# c100_rev_b.net
KiCad netlist of a schematic drawn in EAGLE
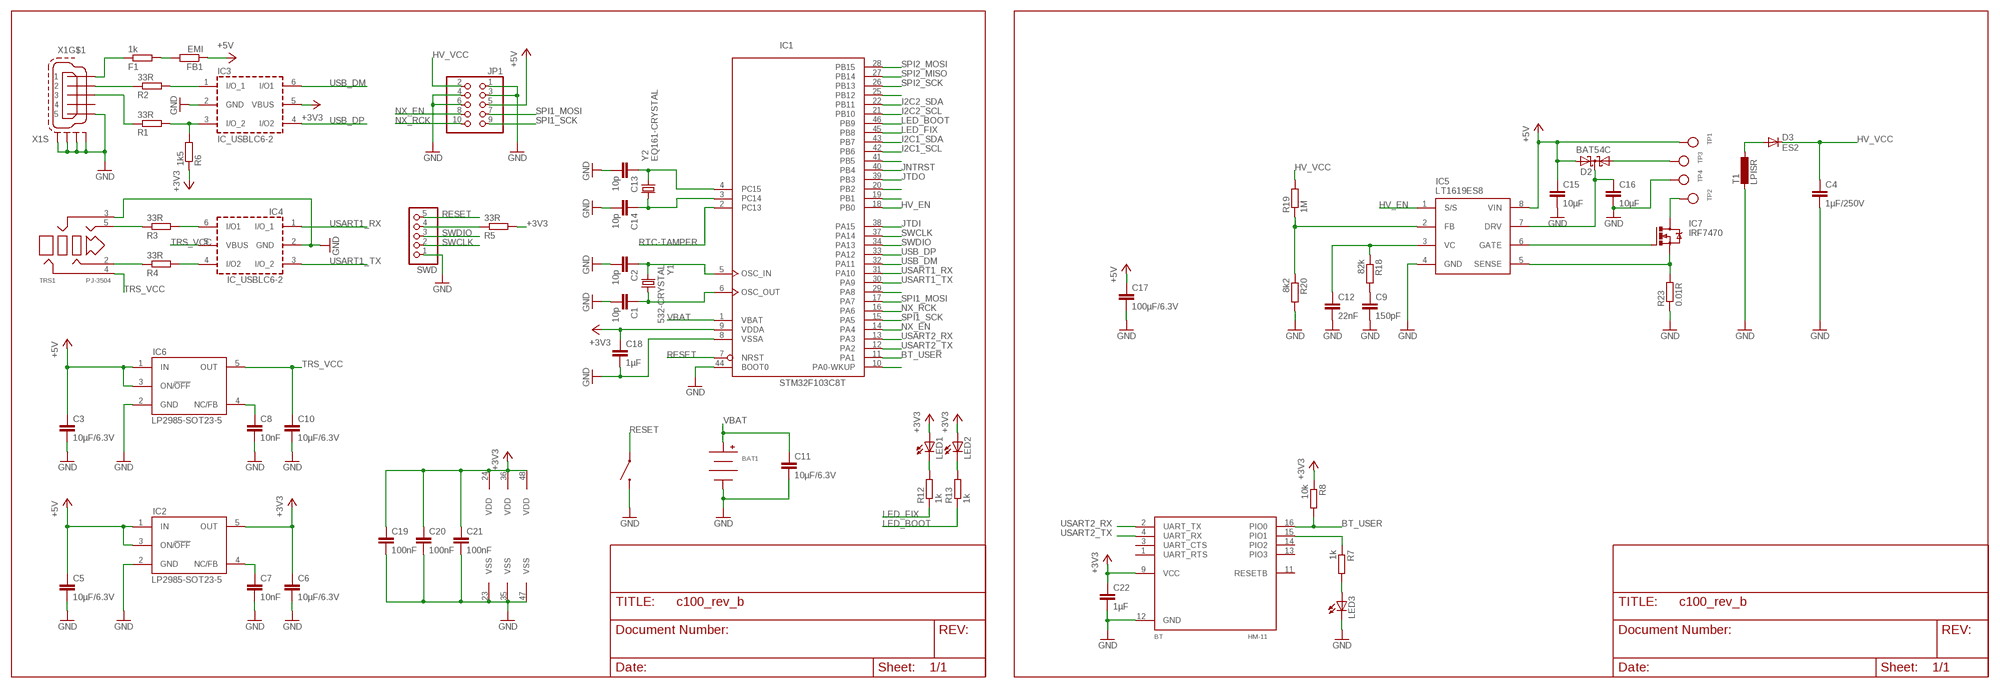
[diagram p0: schematic, sheet 1]

(export (version "E")
  (design (tool "Eeschema 10.0.6"))
  (components
    (comp (ref "BAT1")
      (value "CR1220-HOLDER")
      (footprint "eagle-import:HARWIN-CR1220")
      (libsource (lib "eagle-import") (part "CR1220-HOLDER"))
    )
    (comp (ref "BT")
      (value "HM-11")
      (footprint "eagle-import:HM-11")
      (libsource (lib "eagle-import") (part "HM-11"))
    )
    (comp (ref "C1")
      (value "10p")
      (footprint "eagle-import:C0603")
      (libsource (lib "eagle-import") (part "C-EUC0603"))
    )
    (comp (ref "C2")
      (value "10p")
      (footprint "eagle-import:C0603")
      (libsource (lib "eagle-import") (part "C-EUC0603"))
    )
    (comp (ref "C3")
      (value "10µF/6.3V")
      (footprint "eagle-import:C0603")
      (libsource (lib "eagle-import") (part "C-EUC0603"))
    )
    (comp (ref "C4")
      (value "1µF/250V")
      (footprint "eagle-import:C2220K")
      (libsource (lib "eagle-import") (part "C-EUC2220K"))
    )
    (comp (ref "C5")
      (value "10µF/6.3V")
      (footprint "eagle-import:C0603")
      (libsource (lib "eagle-import") (part "C-EUC0603"))
    )
    (comp (ref "C6")
      (value "10µF/6.3V")
      (footprint "eagle-import:C0603")
      (libsource (lib "eagle-import") (part "C-EUC0603"))
    )
    (comp (ref "C7")
      (value "10nF")
      (footprint "eagle-import:C0603")
      (libsource (lib "eagle-import") (part "C-EUC0603"))
    )
    (comp (ref "C8")
      (value "10nF")
      (footprint "eagle-import:C0603")
      (libsource (lib "eagle-import") (part "C-EUC0603"))
    )
    (comp (ref "C9")
      (value "150pF")
      (footprint "eagle-import:C0603")
      (libsource (lib "eagle-import") (part "C-EUC0603"))
    )
    (comp (ref "C10")
      (value "10µF/6.3V")
      (footprint "eagle-import:C0603")
      (libsource (lib "eagle-import") (part "C-EUC0603"))
    )
    (comp (ref "C11")
      (value "10µF/6.3V")
      (footprint "eagle-import:C0603")
      (libsource (lib "eagle-import") (part "C-EUC0603"))
    )
    (comp (ref "C12")
      (value "22nF")
      (footprint "eagle-import:C0603")
      (libsource (lib "eagle-import") (part "C-EUC0603"))
    )
    (comp (ref "C13")
      (value "10p")
      (footprint "eagle-import:C0603")
      (libsource (lib "eagle-import") (part "C-EUC0603"))
    )
    (comp (ref "C14")
      (value "10p")
      (footprint "eagle-import:C0603")
      (libsource (lib "eagle-import") (part "C-EUC0603"))
    )
    (comp (ref "C15")
      (value "10µF")
      (footprint "eagle-import:C0603")
      (libsource (lib "eagle-import") (part "C-EUC0603"))
    )
    (comp (ref "C16")
      (value "10µF")
      (footprint "eagle-import:C0603")
      (libsource (lib "eagle-import") (part "C-EUC0603"))
    )
    (comp (ref "C17")
      (value "100µF/6.3V")
      (footprint "eagle-import:C1210")
      (libsource (lib "eagle-import") (part "C-EUC1210"))
    )
    (comp (ref "C18")
      (value "1µF")
      (footprint "eagle-import:C0603")
      (libsource (lib "eagle-import") (part "C-EUC0603"))
    )
    (comp (ref "C19")
      (value "100nF")
      (footprint "eagle-import:C0603")
      (libsource (lib "eagle-import") (part "C-EUC0603"))
    )
    (comp (ref "C20")
      (value "100nF")
      (footprint "eagle-import:C0603")
      (libsource (lib "eagle-import") (part "C-EUC0603"))
    )
    (comp (ref "C21")
      (value "100nF")
      (footprint "eagle-import:C0603")
      (libsource (lib "eagle-import") (part "C-EUC0603"))
    )
    (comp (ref "C22")
      (value "1µF")
      (footprint "eagle-import:C0603")
      (libsource (lib "eagle-import") (part "C-EUC0603"))
    )
    (comp (ref "D2")
      (value "BAT54C")
      (footprint "eagle-import:SOT23")
      (libsource (lib "eagle-import") (part "BAT54C"))
    )
    (comp (ref "D3")
      (value "ES2")
      (footprint "eagle-import:DO-214AA")
      (libsource (lib "eagle-import") (part "ES2"))
    )
    (comp (ref "F1")
      (value "1k")
      (footprint "eagle-import:R0603")
      (libsource (lib "eagle-import") (part "R-EU_R0603"))
    )
    (comp (ref "FB1")
      (value "EMI")
      (footprint "eagle-import:R0603")
      (libsource (lib "eagle-import") (part "R-EU_R0603"))
    )
    (comp (ref "IC1")
      (value "STM32F103C8T")
      (footprint "eagle-import:LQFP48")
      (libsource (lib "eagle-import") (part "STM32F103CT8"))
    )
    (comp (ref "IC2")
      (value "LP2985-SOT23-5")
      (footprint "eagle-import:SOT23-5")
      (libsource (lib "eagle-import") (part "LP2985-SOT23-5"))
    )
    (comp (ref "IC3")
      (value "IC_USBLC6-2")
      (footprint "eagle-import:SOT-23-6L")
      (libsource (lib "eagle-import") (part "IC_USBLC6-2"))
    )
    (comp (ref "IC4")
      (value "IC_USBLC6-2")
      (footprint "eagle-import:SOT-23-6L")
      (libsource (lib "eagle-import") (part "IC_USBLC6-2"))
    )
    (comp (ref "IC5")
      (value "LT1619ES8")
      (footprint "eagle-import:SO8")
      (libsource (lib "eagle-import") (part "LT1619ES8"))
    )
    (comp (ref "IC6")
      (value "LP2985-SOT23-5")
      (footprint "eagle-import:SOT23-5")
      (libsource (lib "eagle-import") (part "LP2985-SOT23-5"))
    )
    (comp (ref "IC7")
      (value "IRF7470")
      (footprint "eagle-import:SO8")
      (libsource (lib "eagle-import") (part "IRF7470"))
    )
    (comp (ref "ISP")
      (value "TACT-SWITCH-40-40")
      (footprint "eagle-import:40-40")
      (libsource (lib "eagle-import") (part "TACT-SWITCH-40-40"))
    )
    (comp (ref "JP1")
      (value "PINHD-2X5_2.54-SMD")
      (footprint "eagle-import:2X05SMD")
      (libsource (lib "eagle-import") (part "PINHD-2X5_2.54-SMD"))
    )
    (comp (ref "LED1")
      (value "LEDCHIP-LED0603")
      (footprint "eagle-import:CHIP-LED0603")
      (libsource (lib "eagle-import") (part "LEDCHIP-LED0603"))
    )
    (comp (ref "LED2")
      (value "LEDCHIP-LED0603")
      (footprint "eagle-import:CHIP-LED0603")
      (libsource (lib "eagle-import") (part "LEDCHIP-LED0603"))
    )
    (comp (ref "LED3")
      (value "LEDCHIP-LED0603")
      (footprint "eagle-import:CHIP-LED0603")
      (libsource (lib "eagle-import") (part "LEDCHIP-LED0603"))
    )
    (comp (ref "R1")
      (value "33R")
      (footprint "eagle-import:R0603")
      (libsource (lib "eagle-import") (part "R-EU_R0603"))
    )
    (comp (ref "R2")
      (value "33R")
      (footprint "eagle-import:R0603")
      (libsource (lib "eagle-import") (part "R-EU_R0603"))
    )
    (comp (ref "R3")
      (value "33R")
      (footprint "eagle-import:R0603")
      (libsource (lib "eagle-import") (part "R-EU_R0603"))
    )
    (comp (ref "R4")
      (value "33R")
      (footprint "eagle-import:R0603")
      (libsource (lib "eagle-import") (part "R-EU_R0603"))
    )
    (comp (ref "R5")
      (value "33R")
      (footprint "eagle-import:R0603")
      (libsource (lib "eagle-import") (part "R-EU_R0603"))
    )
    (comp (ref "R6")
      (value "1k5")
      (footprint "eagle-import:R0603")
      (libsource (lib "eagle-import") (part "R-EU_R0603"))
    )
    (comp (ref "R7")
      (value "1k")
      (footprint "eagle-import:R0603")
      (libsource (lib "eagle-import") (part "R-EU_R0603"))
    )
    (comp (ref "R8")
      (value "10k")
      (footprint "eagle-import:R0603")
      (libsource (lib "eagle-import") (part "R-EU_R0603"))
    )
    (comp (ref "R12")
      (value "1k")
      (footprint "eagle-import:R0603")
      (libsource (lib "eagle-import") (part "R-EU_R0603"))
    )
    (comp (ref "R13")
      (value "1k")
      (footprint "eagle-import:R0603")
      (libsource (lib "eagle-import") (part "R-EU_R0603"))
    )
    (comp (ref "R18")
      (value "82k")
      (footprint "eagle-import:R0603")
      (libsource (lib "eagle-import") (part "R-EU_R0603"))
    )
    (comp (ref "R19")
      (value "1M")
      (footprint "eagle-import:M1206")
      (libsource (lib "eagle-import") (part "R-EU_M1206"))
    )
    (comp (ref "R20")
      (value "8k2")
      (footprint "eagle-import:R0603")
      (libsource (lib "eagle-import") (part "R-EU_R0603"))
    )
    (comp (ref "R23")
      (value "0.01R")
      (footprint "eagle-import:R1206")
      (libsource (lib "eagle-import") (part "R-EU_R1206"))
    )
    (comp (ref "SWD")
      (value "HEADER-1X5ROUND")
      (footprint "eagle-import:1X05_ROUND")
      (libsource (lib "eagle-import") (part "HEADER-1X5ROUND"))
    )
    (comp (ref "T1")
      (value "LPISR")
      (footprint "eagle-import:PISR")
      (libsource (lib "eagle-import") (part "LPISR"))
    )
    (comp (ref "TP1")
      (value "TESTPOINTROUND2MM")
      (footprint "eagle-import:TESTPOINT_ROUND_2MM")
      (libsource (lib "eagle-import") (part "TESTPOINTROUND2MM"))
    )
    (comp (ref "TP2")
      (value "TESTPOINTROUND2MM")
      (footprint "eagle-import:TESTPOINT_ROUND_2MM")
      (libsource (lib "eagle-import") (part "TESTPOINTROUND2MM"))
    )
    (comp (ref "TP3")
      (value "TESTPOINTROUND2MM")
      (footprint "eagle-import:TESTPOINT_ROUND_2MM")
      (libsource (lib "eagle-import") (part "TESTPOINTROUND2MM"))
    )
    (comp (ref "TP4")
      (value "TESTPOINTROUND2MM")
      (footprint "eagle-import:TESTPOINT_ROUND_2MM")
      (libsource (lib "eagle-import") (part "TESTPOINTROUND2MM"))
    )
    (comp (ref "TRS1")
      (value "PJ-3504")
      (footprint "eagle-import:YD-PJ-3504")
      (libsource (lib "eagle-import") (part "PJ-3504"))
    )
    (comp (ref "X1")
      (value "MINI-USB-SCHIELD-32005-201")
      (footprint "eagle-import:32005-201")
      (libsource (lib "eagle-import") (part "MINI-USB-SCHIELD-32005-201"))
    )
    (comp (ref "Y1")
      (value "532-CRYSTAL")
      (footprint "eagle-import:2PIN50X32")
      (libsource (lib "eagle-import") (part "532-CRYSTAL"))
    )
    (comp (ref "Y2")
      (value "EQ161-CRYSTAL")
      (footprint "eagle-import:EQ161")
      (libsource (lib "eagle-import") (part "EQ161-CRYSTAL"))
    )
  )
  (nets
    (net (code "1") (name "+3V3") (class "Default")
      (node (ref "BT") (pin "9") (pinfunction "VCC_9") (pintype "bidirectional"))
      (node (ref "C18") (pin "1") (pinfunction "1_1") (pintype "passive"))
      (node (ref "C19") (pin "1") (pinfunction "1_1") (pintype "passive"))
      (node (ref "C20") (pin "1") (pinfunction "1_1") (pintype "passive"))
      (node (ref "C21") (pin "1") (pinfunction "1_1") (pintype "passive"))
      (node (ref "C22") (pin "1") (pinfunction "1_1") (pintype "passive"))
      (node (ref "C6") (pin "1") (pinfunction "1_1") (pintype "passive"))
      (node (ref "IC1") (pin "24") (pinfunction "VDD_24") (pintype "power_in"))
      (node (ref "IC1") (pin "36") (pinfunction "VDD_36") (pintype "power_in"))
      (node (ref "IC1") (pin "48") (pinfunction "VDD_48") (pintype "power_in"))
      (node (ref "IC1") (pin "9") (pinfunction "VDDA_9") (pintype "power_in"))
      (node (ref "IC2") (pin "5") (pinfunction "OUT_5") (pintype "bidirectional"))
      (node (ref "IC3") (pin "5") (pinfunction "VBUS_5") (pintype "bidirectional"))
      (node (ref "LED1") (pin "A") (pinfunction "A_A") (pintype "passive"))
      (node (ref "LED2") (pin "A") (pinfunction "A_A") (pintype "passive"))
      (node (ref "R5") (pin "2") (pinfunction "2_2") (pintype "passive"))
      (node (ref "R6") (pin "1") (pinfunction "1_1") (pintype "passive"))
      (node (ref "R8") (pin "1") (pinfunction "1_1") (pintype "passive"))
    )
    (net (code "2") (name "+5V") (class "Default")
      (node (ref "C15") (pin "1") (pinfunction "1_1") (pintype "passive"))
      (node (ref "C17") (pin "1") (pinfunction "1_1") (pintype "passive"))
      (node (ref "C3") (pin "1") (pinfunction "1_1") (pintype "passive"))
      (node (ref "C5") (pin "1") (pinfunction "1_1") (pintype "passive"))
      (node (ref "D2") (pin "2") (pinfunction "A2_2") (pintype "passive"))
      (node (ref "FB1") (pin "1") (pinfunction "1_1") (pintype "passive"))
      (node (ref "IC2") (pin "1") (pinfunction "IN_1") (pintype "bidirectional"))
      (node (ref "IC2") (pin "3") (pinfunction "ON/~{OFF}_3") (pintype "bidirectional"))
      (node (ref "IC5") (pin "8") (pinfunction "VIN_8") (pintype "bidirectional"))
      (node (ref "IC6") (pin "1") (pinfunction "IN_1") (pintype "bidirectional"))
      (node (ref "IC6") (pin "3") (pinfunction "ON/~{OFF}_3") (pintype "bidirectional"))
      (node (ref "JP1") (pin "5") (pinfunction "5_5") (pintype "passive"))
      (node (ref "TP1") (pin "P$1") (pinfunction "P$1_P$1") (pintype "bidirectional"))
    )
    (net (code "3") (name "/BT_USER") (class "Default")
      (node (ref "BT") (pin "16") (pinfunction "PIO0_16") (pintype "bidirectional"))
      (node (ref "IC1") (pin "11") (pinfunction "PA1_11") (pintype "bidirectional"))
      (node (ref "R8") (pin "2") (pinfunction "2_2") (pintype "passive"))
    )
    (net (code "4") (name "/HV_EN") (class "Default")
      (node (ref "IC1") (pin "18") (pinfunction "PB0_18") (pintype "bidirectional"))
      (node (ref "IC5") (pin "1") (pinfunction "S/S_1") (pintype "bidirectional"))
    )
    (net (code "5") (name "/HV_VCC") (class "Default")
      (node (ref "C4") (pin "1") (pinfunction "1_1") (pintype "passive"))
      (node (ref "D3") (pin "C") (pinfunction "C_C") (pintype "passive"))
      (node (ref "JP1") (pin "2") (pinfunction "2_2") (pintype "passive"))
      (node (ref "R19") (pin "2") (pinfunction "2_2") (pintype "passive"))
    )
    (net (code "6") (name "/I2C1_SCL") (class "Default")
      (node (ref "IC1") (pin "42") (pinfunction "PB6_42") (pintype "bidirectional"))
    )
    (net (code "7") (name "/I2C1_SDA") (class "Default")
      (node (ref "IC1") (pin "43") (pinfunction "PB7_43") (pintype "bidirectional"))
    )
    (net (code "8") (name "/I2C2_SCL") (class "Default")
      (node (ref "IC1") (pin "21") (pinfunction "PB10_21") (pintype "bidirectional"))
    )
    (net (code "9") (name "/I2C2_SDA") (class "Default")
      (node (ref "IC1") (pin "22") (pinfunction "PB11_22") (pintype "bidirectional"))
    )
    (net (code "10") (name "/JNTRST") (class "Default")
      (node (ref "IC1") (pin "40") (pinfunction "PB4_40") (pintype "bidirectional"))
    )
    (net (code "11") (name "/JTDI") (class "Default")
      (node (ref "IC1") (pin "38") (pinfunction "PA15_38") (pintype "bidirectional"))
    )
    (net (code "12") (name "/JTDO") (class "Default")
      (node (ref "IC1") (pin "39") (pinfunction "PB3_39") (pintype "bidirectional"))
    )
    (net (code "13") (name "/LED_BOOT") (class "Default")
      (node (ref "IC1") (pin "46") (pinfunction "PB9_46") (pintype "bidirectional"))
      (node (ref "R13") (pin "1") (pinfunction "1_1") (pintype "passive"))
    )
    (net (code "14") (name "/LED_FIX") (class "Default")
      (node (ref "IC1") (pin "45") (pinfunction "PB8_45") (pintype "bidirectional"))
      (node (ref "R12") (pin "1") (pinfunction "1_1") (pintype "passive"))
    )
    (net (code "15") (name "/NX_EN") (class "Default")
      (node (ref "IC1") (pin "14") (pinfunction "PA4_14") (pintype "bidirectional"))
      (node (ref "JP1") (pin "8") (pinfunction "8_8") (pintype "passive"))
    )
    (net (code "16") (name "/NX_RCK") (class "Default")
      (node (ref "IC1") (pin "16") (pinfunction "PA6_16") (pintype "bidirectional"))
      (node (ref "JP1") (pin "10") (pinfunction "10_10") (pintype "passive"))
    )
    (net (code "17") (name "/RESET") (class "Default")
      (node (ref "IC1") (pin "7") (pinfunction "NRST_7") (pintype "bidirectional"))
      (node (ref "ISP") (pin "3") (pinfunction "P$2_3") (pintype "bidirectional"))
      (node (ref "ISP") (pin "4") (pinfunction "P$2_4") (pintype "bidirectional"))
      (node (ref "SWD") (pin "5") (pinfunction "5_5") (pintype "passive"))
    )
    (net (code "18") (name "/RTC-TAMPER") (class "Default")
      (node (ref "IC1") (pin "2") (pinfunction "PC13_2") (pintype "bidirectional"))
    )
    (net (code "19") (name "/SPI1_MOSI") (class "Default")
      (node (ref "IC1") (pin "17") (pinfunction "PA7_17") (pintype "bidirectional"))
      (node (ref "JP1") (pin "7") (pinfunction "7_7") (pintype "passive"))
    )
    (net (code "20") (name "/SPI1_SCK") (class "Default")
      (node (ref "IC1") (pin "15") (pinfunction "PA5_15") (pintype "bidirectional"))
      (node (ref "JP1") (pin "9") (pinfunction "9_9") (pintype "passive"))
    )
    (net (code "21") (name "/SPI2_MISO") (class "Default")
      (node (ref "IC1") (pin "27") (pinfunction "PB14_27") (pintype "bidirectional"))
    )
    (net (code "22") (name "/SPI2_MOSI") (class "Default")
      (node (ref "IC1") (pin "28") (pinfunction "PB15_28") (pintype "bidirectional"))
    )
    (net (code "23") (name "/SPI2_SCK") (class "Default")
      (node (ref "IC1") (pin "26") (pinfunction "PB13_26") (pintype "bidirectional"))
    )
    (net (code "24") (name "/SWCLK") (class "Default")
      (node (ref "IC1") (pin "37") (pinfunction "PA14_37") (pintype "bidirectional"))
      (node (ref "SWD") (pin "2") (pinfunction "2_2") (pintype "passive"))
    )
    (net (code "25") (name "/SWDIO") (class "Default")
      (node (ref "IC1") (pin "34") (pinfunction "PA13_34") (pintype "bidirectional"))
      (node (ref "SWD") (pin "3") (pinfunction "3_3") (pintype "passive"))
    )
    (net (code "26") (name "/TRS_VCC") (class "Default")
      (node (ref "C10") (pin "1") (pinfunction "1_1") (pintype "passive"))
      (node (ref "IC4") (pin "5") (pinfunction "VBUS_5") (pintype "bidirectional"))
      (node (ref "IC6") (pin "5") (pinfunction "OUT_5") (pintype "bidirectional"))
      (node (ref "TRS1") (pin "4") (pinfunction "4_4") (pintype "bidirectional"))
    )
    (net (code "27") (name "/USART1_RX") (class "Default")
      (node (ref "IC1") (pin "31") (pinfunction "PA10_31") (pintype "bidirectional"))
      (node (ref "IC4") (pin "1") (pinfunction "I/O_1_1") (pintype "bidirectional"))
    )
    (net (code "28") (name "/USART1_TX") (class "Default")
      (node (ref "IC1") (pin "30") (pinfunction "PA9_30") (pintype "bidirectional"))
      (node (ref "IC4") (pin "3") (pinfunction "I/O_2_3") (pintype "bidirectional"))
    )
    (net (code "29") (name "/USART2_RX") (class "Default")
      (node (ref "BT") (pin "2") (pinfunction "UART_TX_2") (pintype "bidirectional"))
      (node (ref "IC1") (pin "13") (pinfunction "PA3_13") (pintype "bidirectional"))
    )
    (net (code "30") (name "/USART2_TX") (class "Default")
      (node (ref "BT") (pin "4") (pinfunction "UART_RX_4") (pintype "bidirectional"))
      (node (ref "IC1") (pin "12") (pinfunction "PA2_12") (pintype "bidirectional"))
    )
    (net (code "31") (name "/USB_DM") (class "Default")
      (node (ref "IC1") (pin "32") (pinfunction "PA11_32") (pintype "bidirectional"))
      (node (ref "IC3") (pin "6") (pinfunction "I/O1_6") (pintype "bidirectional"))
    )
    (net (code "32") (name "/USB_DP") (class "Default")
      (node (ref "IC1") (pin "33") (pinfunction "PA12_33") (pintype "bidirectional"))
      (node (ref "IC3") (pin "4") (pinfunction "I/O2_4") (pintype "bidirectional"))
    )
    (net (code "33") (name "/VBAT") (class "Default")
      (node (ref "BAT1") (pin "POS") (pinfunction "POS_POS") (pintype "bidirectional"))
      (node (ref "C11") (pin "1") (pinfunction "1_1") (pintype "passive"))
      (node (ref "IC1") (pin "1") (pinfunction "VBAT_1") (pintype "power_in"))
    )
    (net (code "34") (name "GND") (class "Default")
      (node (ref "BAT1") (pin "NEG") (pinfunction "NEG_NEG") (pintype "bidirectional"))
      (node (ref "BT") (pin "12") (pinfunction "GND_12") (pintype "bidirectional"))
      (node (ref "C1") (pin "2") (pinfunction "2_2") (pintype "passive"))
      (node (ref "C10") (pin "2") (pinfunction "2_2") (pintype "passive"))
      (node (ref "C11") (pin "2") (pinfunction "2_2") (pintype "passive"))
      (node (ref "C12") (pin "2") (pinfunction "2_2") (pintype "passive"))
      (node (ref "C13") (pin "2") (pinfunction "2_2") (pintype "passive"))
      (node (ref "C14") (pin "2") (pinfunction "2_2") (pintype "passive"))
      (node (ref "C15") (pin "2") (pinfunction "2_2") (pintype "passive"))
      (node (ref "C16") (pin "2") (pinfunction "2_2") (pintype "passive"))
      (node (ref "C17") (pin "2") (pinfunction "2_2") (pintype "passive"))
      (node (ref "C18") (pin "2") (pinfunction "2_2") (pintype "passive"))
      (node (ref "C19") (pin "2") (pinfunction "2_2") (pintype "passive"))
      (node (ref "C2") (pin "2") (pinfunction "2_2") (pintype "passive"))
      (node (ref "C20") (pin "2") (pinfunction "2_2") (pintype "passive"))
      (node (ref "C21") (pin "2") (pinfunction "2_2") (pintype "passive"))
      (node (ref "C22") (pin "2") (pinfunction "2_2") (pintype "passive"))
      (node (ref "C3") (pin "2") (pinfunction "2_2") (pintype "passive"))
      (node (ref "C4") (pin "2") (pinfunction "2_2") (pintype "passive"))
      (node (ref "C5") (pin "2") (pinfunction "2_2") (pintype "passive"))
      (node (ref "C6") (pin "2") (pinfunction "2_2") (pintype "passive"))
      (node (ref "C7") (pin "2") (pinfunction "2_2") (pintype "passive"))
      (node (ref "C8") (pin "2") (pinfunction "2_2") (pintype "passive"))
      (node (ref "C9") (pin "2") (pinfunction "2_2") (pintype "passive"))
      (node (ref "IC1") (pin "23") (pinfunction "VSS_23") (pintype "power_in"))
      (node (ref "IC1") (pin "35") (pinfunction "VSS_35") (pintype "power_in"))
      (node (ref "IC1") (pin "44") (pinfunction "BOOT0_44") (pintype "input"))
      (node (ref "IC1") (pin "47") (pinfunction "VSS_47") (pintype "power_in"))
      (node (ref "IC1") (pin "8") (pinfunction "VSSA_8") (pintype "power_in"))
      (node (ref "IC2") (pin "2") (pinfunction "GND_2") (pintype "bidirectional"))
      (node (ref "IC3") (pin "2") (pinfunction "GND_2") (pintype "bidirectional"))
      (node (ref "IC4") (pin "2") (pinfunction "GND_2") (pintype "bidirectional"))
      (node (ref "IC5") (pin "4") (pinfunction "GND_4") (pintype "bidirectional"))
      (node (ref "IC6") (pin "2") (pinfunction "GND_2") (pintype "bidirectional"))
      (node (ref "ISP") (pin "1") (pinfunction "P$1_1") (pintype "bidirectional"))
      (node (ref "ISP") (pin "2") (pinfunction "P$1_2") (pintype "bidirectional"))
      (node (ref "JP1") (pin "1") (pinfunction "1_1") (pintype "passive"))
      (node (ref "JP1") (pin "3") (pinfunction "3_3") (pintype "passive"))
      (node (ref "JP1") (pin "4") (pinfunction "4_4") (pintype "passive"))
      (node (ref "JP1") (pin "6") (pinfunction "6_6") (pintype "passive"))
      (node (ref "LED3") (pin "C") (pinfunction "C_C") (pintype "passive"))
      (node (ref "R20") (pin "2") (pinfunction "2_2") (pintype "passive"))
      (node (ref "R23") (pin "1") (pinfunction "1_1") (pintype "passive"))
      (node (ref "SWD") (pin "1") (pinfunction "1_1") (pintype "passive"))
      (node (ref "T1") (pin "P$2") (pinfunction "2_P$2") (pintype "passive"))
      (node (ref "TP4") (pin "P$1") (pinfunction "P$1_P$1") (pintype "bidirectional"))
      (node (ref "TRS1") (pin "3") (pinfunction "3_3") (pintype "bidirectional"))
      (node (ref "X1") (pin "5") (pinfunction "5_5") (pintype "passive"))
      (node (ref "X1") (pin "M1") (pinfunction "S1_M1") (pintype "passive"))
      (node (ref "X1") (pin "M2") (pinfunction "S2_M2") (pintype "passive"))
      (node (ref "X1") (pin "M3") (pinfunction "S3_M3") (pintype "passive"))
      (node (ref "X1") (pin "M4") (pinfunction "S4_M4") (pintype "passive"))
    )
    (net (code "35") (name "Net-(BT-PIO1)") (class "Default")
      (node (ref "BT") (pin "15") (pinfunction "PIO1_15") (pintype "bidirectional"))
      (node (ref "R7") (pin "1") (pinfunction "1_1") (pintype "passive"))
    )
    (net (code "36") (name "Net-(C9-Pad1)") (class "Default")
      (node (ref "C9") (pin "1") (pinfunction "1_1") (pintype "passive"))
      (node (ref "R18") (pin "2") (pinfunction "2_2") (pintype "passive"))
    )
    (net (code "37") (name "Net-(D2-A1)") (class "Default")
      (node (ref "D2") (pin "1") (pinfunction "A1_1") (pintype "passive"))
      (node (ref "TP3") (pin "P$1") (pinfunction "P$1_P$1") (pintype "bidirectional"))
    )
    (net (code "38") (name "Net-(D2-CC)") (class "Default")
      (node (ref "C16") (pin "1") (pinfunction "1_1") (pintype "passive"))
      (node (ref "D2") (pin "3") (pinfunction "CC_3") (pintype "passive"))
      (node (ref "IC5") (pin "7") (pinfunction "DRV_7") (pintype "bidirectional"))
    )
    (net (code "39") (name "Net-(F1-Pad1)") (class "Default")
      (node (ref "F1") (pin "1") (pinfunction "1_1") (pintype "passive"))
      (node (ref "X1") (pin "1") (pinfunction "1_1") (pintype "passive"))
    )
    (net (code "40") (name "Net-(F1-Pad2)") (class "Default")
      (node (ref "F1") (pin "2") (pinfunction "2_2") (pintype "passive"))
      (node (ref "FB1") (pin "2") (pinfunction "2_2") (pintype "passive"))
    )
    (net (code "41") (name "Net-(IC1A-OSC_IN)") (class "Default")
      (node (ref "C2") (pin "1") (pinfunction "1_1") (pintype "passive"))
      (node (ref "IC1") (pin "5") (pinfunction "OSC_IN_5") (pintype "bidirectional"))
      (node (ref "Y1") (pin "P$2") (pinfunction "2_P$2") (pintype "passive"))
    )
    (net (code "42") (name "Net-(IC1A-OSC_OUT)") (class "Default")
      (node (ref "C1") (pin "1") (pinfunction "1_1") (pintype "passive"))
      (node (ref "IC1") (pin "6") (pinfunction "OSC_OUT_6") (pintype "bidirectional"))
      (node (ref "Y1") (pin "P$1") (pinfunction "1_P$1") (pintype "passive"))
    )
    (net (code "43") (name "Net-(IC1A-PC14)") (class "Default")
      (node (ref "C14") (pin "1") (pinfunction "1_1") (pintype "passive"))
      (node (ref "IC1") (pin "3") (pinfunction "PC14_3") (pintype "bidirectional"))
      (node (ref "Y2") (pin "P$2") (pinfunction "2_P$2") (pintype "passive"))
    )
    (net (code "44") (name "Net-(IC1A-PC15)") (class "Default")
      (node (ref "C13") (pin "1") (pinfunction "1_1") (pintype "passive"))
      (node (ref "IC1") (pin "4") (pinfunction "PC15_4") (pintype "bidirectional"))
      (node (ref "Y2") (pin "P$1") (pinfunction "1_P$1") (pintype "passive"))
    )
    (net (code "45") (name "Net-(IC2-NC{slash}FB)") (class "Default")
      (node (ref "C7") (pin "1") (pinfunction "1_1") (pintype "passive"))
      (node (ref "IC2") (pin "4") (pinfunction "NC/FB_4") (pintype "bidirectional"))
    )
    (net (code "46") (name "Net-(IC3-I{slash}O_1)") (class "Default")
      (node (ref "IC3") (pin "1") (pinfunction "I/O_1_1") (pintype "bidirectional"))
      (node (ref "R2") (pin "2") (pinfunction "2_2") (pintype "passive"))
    )
    (net (code "47") (name "Net-(IC3-I{slash}O_2)") (class "Default")
      (node (ref "IC3") (pin "3") (pinfunction "I/O_2_3") (pintype "bidirectional"))
      (node (ref "R1") (pin "2") (pinfunction "2_2") (pintype "passive"))
      (node (ref "R6") (pin "2") (pinfunction "2_2") (pintype "passive"))
    )
    (net (code "48") (name "Net-(IC4-I{slash}O1)") (class "Default")
      (node (ref "IC4") (pin "6") (pinfunction "I/O1_6") (pintype "bidirectional"))
      (node (ref "R3") (pin "2") (pinfunction "2_2") (pintype "passive"))
    )
    (net (code "49") (name "Net-(IC4-I{slash}O2)") (class "Default")
      (node (ref "IC4") (pin "4") (pinfunction "I/O2_4") (pintype "bidirectional"))
      (node (ref "R4") (pin "2") (pinfunction "2_2") (pintype "passive"))
    )
    (net (code "50") (name "Net-(IC5-FB)") (class "Default")
      (node (ref "IC5") (pin "2") (pinfunction "FB_2") (pintype "bidirectional"))
      (node (ref "R19") (pin "1") (pinfunction "1_1") (pintype "passive"))
      (node (ref "R20") (pin "1") (pinfunction "1_1") (pintype "passive"))
    )
    (net (code "51") (name "Net-(IC5-GATE)") (class "Default")
      (node (ref "IC5") (pin "6") (pinfunction "GATE_6") (pintype "bidirectional"))
      (node (ref "IC7") (pin "4") (pinfunction "G_4") (pintype "passive"))
    )
    (net (code "52") (name "Net-(IC5-SENSE)") (class "Default")
      (node (ref "IC5") (pin "5") (pinfunction "SENSE_5") (pintype "bidirectional"))
      (node (ref "IC7") (pin "1") (pinfunction "S_1") (pintype "passive"))
      (node (ref "IC7") (pin "2") (pinfunction "S_2") (pintype "passive"))
      (node (ref "IC7") (pin "3") (pinfunction "S_3") (pintype "passive"))
      (node (ref "R23") (pin "2") (pinfunction "2_2") (pintype "passive"))
    )
    (net (code "53") (name "Net-(IC5-VC)") (class "Default")
      (node (ref "C12") (pin "1") (pinfunction "1_1") (pintype "passive"))
      (node (ref "IC5") (pin "3") (pinfunction "VC_3") (pintype "bidirectional"))
      (node (ref "R18") (pin "1") (pinfunction "1_1") (pintype "passive"))
    )
    (net (code "54") (name "Net-(IC6-NC{slash}FB)") (class "Default")
      (node (ref "C8") (pin "1") (pinfunction "1_1") (pintype "passive"))
      (node (ref "IC6") (pin "4") (pinfunction "NC/FB_4") (pintype "bidirectional"))
    )
    (net (code "55") (name "Net-(IC7-D-Pad5)") (class "Default")
      (node (ref "IC7") (pin "5") (pinfunction "D_5") (pintype "passive"))
      (node (ref "IC7") (pin "6") (pinfunction "D_6") (pintype "passive"))
      (node (ref "IC7") (pin "7") (pinfunction "D_7") (pintype "passive"))
      (node (ref "IC7") (pin "8") (pinfunction "D_8") (pintype "passive"))
      (node (ref "TP2") (pin "P$1") (pinfunction "P$1_P$1") (pintype "bidirectional"))
    )
    (net (code "56") (name "Net-(LED1-PadC)") (class "Default")
      (node (ref "LED1") (pin "C") (pinfunction "C_C") (pintype "passive"))
      (node (ref "R12") (pin "2") (pinfunction "2_2") (pintype "passive"))
    )
    (net (code "57") (name "Net-(LED2-PadC)") (class "Default")
      (node (ref "LED2") (pin "C") (pinfunction "C_C") (pintype "passive"))
      (node (ref "R13") (pin "2") (pinfunction "2_2") (pintype "passive"))
    )
    (net (code "58") (name "Net-(LED3-PadA)") (class "Default")
      (node (ref "LED3") (pin "A") (pinfunction "A_A") (pintype "passive"))
      (node (ref "R7") (pin "2") (pinfunction "2_2") (pintype "passive"))
    )
    (net (code "59") (name "Net-(R1-Pad1)") (class "Default")
      (node (ref "R1") (pin "1") (pinfunction "1_1") (pintype "passive"))
      (node (ref "X1") (pin "3") (pinfunction "3_3") (pintype "passive"))
    )
    (net (code "60") (name "Net-(R2-Pad1)") (class "Default")
      (node (ref "R2") (pin "1") (pinfunction "1_1") (pintype "passive"))
      (node (ref "X1") (pin "2") (pinfunction "2_2") (pintype "passive"))
    )
    (net (code "61") (name "Net-(R3-Pad1)") (class "Default")
      (node (ref "R3") (pin "1") (pinfunction "1_1") (pintype "passive"))
      (node (ref "TRS1") (pin "5") (pinfunction "5_5") (pintype "bidirectional"))
    )
    (net (code "62") (name "Net-(R4-Pad1)") (class "Default")
      (node (ref "R4") (pin "1") (pinfunction "1_1") (pintype "passive"))
      (node (ref "TRS1") (pin "2") (pinfunction "2_2") (pintype "bidirectional"))
    )
    (net (code "63") (name "Net-(R5-Pad1)") (class "Default")
      (node (ref "R5") (pin "1") (pinfunction "1_1") (pintype "passive"))
      (node (ref "SWD") (pin "4") (pinfunction "4_4") (pintype "passive"))
    )
    (net (code "64") (name "Net-(T1-1)") (class "Default")
      (node (ref "D3") (pin "A") (pinfunction "A_A") (pintype "passive"))
      (node (ref "T1") (pin "P$1") (pinfunction "1_P$1") (pintype "passive"))
    )
    (net (code "65") (name "unconnected-(BT-PIO2-Pad14)") (class "Default")
      (node (ref "BT") (pin "14") (pinfunction "PIO2_14") (pintype "bidirectional"))
    )
    (net (code "66") (name "unconnected-(BT-PIO3-Pad13)") (class "Default")
      (node (ref "BT") (pin "13") (pinfunction "PIO3_13") (pintype "bidirectional"))
    )
    (net (code "67") (name "unconnected-(BT-RESETB-Pad11)") (class "Default")
      (node (ref "BT") (pin "11") (pinfunction "RESETB_11") (pintype "bidirectional"))
    )
    (net (code "68") (name "unconnected-(BT-UART_CTS-Pad3)") (class "Default")
      (node (ref "BT") (pin "3") (pinfunction "UART_CTS_3") (pintype "bidirectional"))
    )
    (net (code "69") (name "unconnected-(BT-UART_RTS-Pad1)") (class "Default")
      (node (ref "BT") (pin "1") (pinfunction "UART_RTS_1") (pintype "bidirectional"))
    )
    (net (code "70") (name "unconnected-(IC1A-PA0-WKUP-Pad10)") (class "Default")
      (node (ref "IC1") (pin "10") (pinfunction "PA0-WKUP_10") (pintype "bidirectional"))
    )
    (net (code "71") (name "unconnected-(IC1A-PA8-Pad29)") (class "Default")
      (node (ref "IC1") (pin "29") (pinfunction "PA8_29") (pintype "bidirectional"))
    )
    (net (code "72") (name "unconnected-(IC1A-PB1-Pad19)") (class "Default")
      (node (ref "IC1") (pin "19") (pinfunction "PB1_19") (pintype "bidirectional"))
    )
    (net (code "73") (name "unconnected-(IC1A-PB2-Pad20)") (class "Default")
      (node (ref "IC1") (pin "20") (pinfunction "PB2_20") (pintype "bidirectional"))
    )
    (net (code "74") (name "unconnected-(IC1A-PB5-Pad41)") (class "Default")
      (node (ref "IC1") (pin "41") (pinfunction "PB5_41") (pintype "bidirectional"))
    )
    (net (code "75") (name "unconnected-(IC1A-PB12-Pad25)") (class "Default")
      (node (ref "IC1") (pin "25") (pinfunction "PB12_25") (pintype "bidirectional"))
    )
    (net (code "76") (name "unconnected-(X1-Pad4)") (class "Default")
      (node (ref "X1") (pin "4") (pinfunction "4_4") (pintype "passive"))
    )
  )
)
